# Interface.net
KiCad netlist of a schematic drawn in Altium Designer
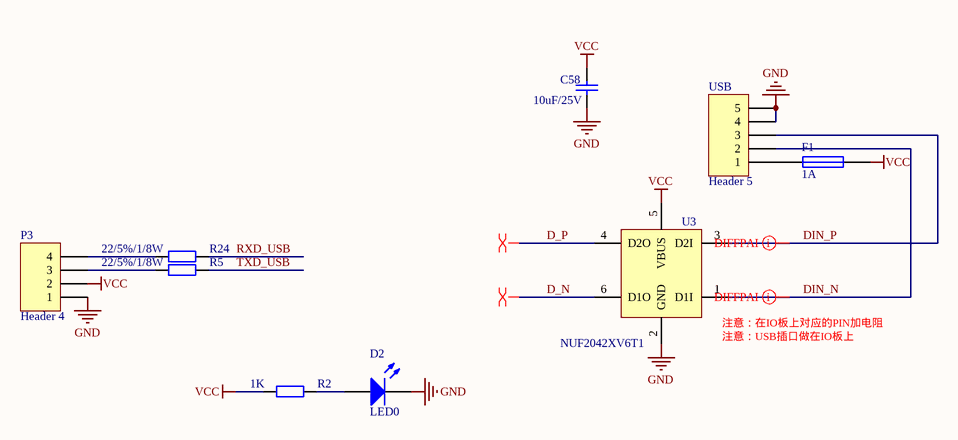
[diagram p0: Interface.SchDoc]

(export (version "E")
  (design (tool "Eeschema 10.0.6"))
  (components
    (comp (ref "C58")
      (value "10uF/25V")
      (footprint "0603C")
      (description "Capacitor")
      (fields (field (name "PUBLISHER") "Altium Limited"))
      (libsource (lib "Miscellaneous Devices") (part "Cap"))
    )
    (comp (ref "D2")
      (value "LED0")
      (footprint "0603LED")
      (description "Typical INFRARED GaAs LED")
      (fields (field (name "PUBLISHER") "Altium Limited"))
      (libsource (lib "Miscellaneous Devices") (part "LED0"))
    )
    (comp (ref "F1")
      (value "1A")
      (footprint "0805R")
      (description "Fuse")
      (fields (field (name "PUBLISHER") "Altium Limited"))
      (libsource (lib "Miscellaneous Devices") (part "Fuse 1"))
    )
    (comp (ref "P3")
      (value "Header 4")
      (footprint "HDR1X4")
      (description "Header, 4-Pin")
      (fields (field (name "PUBLISHER") "Altium Limited"))
      (libsource (lib "Miscellaneous Connectors") (part "Header 4"))
    )
    (comp (ref "R2")
      (value "1K")
      (footprint "0402R")
      (description "Resistor SMD - IEC symbol version")
      (libsource (lib "SX1276_e266v02a") (part "Resistor"))
    )
    (comp (ref "R5")
      (value "22/5%/1/8W")
      (footprint "0402R")
      (description "Resistor SMD - IEC symbol version")
      (libsource (lib "SX1276_e266v02a") (part "Resistor"))
    )
    (comp (ref "R24")
      (value "22/5%/1/8W")
      (footprint "0402R")
      (description "Resistor SMD - IEC symbol version")
      (libsource (lib "SX1276_e266v02a") (part "Resistor"))
    )
    (comp (ref "U3")
      (value "NUF2042XV6T1")
      (footprint "SOT563-6")
      (libsource (lib "Myself_1") (part "NUF2042XV6T1"))
    )
    (comp (ref "USB")
      (value "Header 5")
      (footprint "Micro_USB_PH")
      (description "Header, 5-Pin")
      (fields (field (name "PUBLISHER") "Altium Limited"))
      (libsource (lib "Miscellaneous Connectors") (part "Header 5"))
    )
  )
  (nets
    (net (code "1") (name "/DIN_N") (class "Default")
      (node (ref "U3") (pin "1") (pinfunction "D1I_1") (pintype "passive"))
      (node (ref "USB") (pin "2") (pinfunction "2_2") (pintype "passive"))
    )
    (net (code "2") (name "/DIN_P") (class "Default")
      (node (ref "U3") (pin "3") (pinfunction "D2I_3") (pintype "passive"))
      (node (ref "USB") (pin "3") (pinfunction "3_3") (pintype "passive"))
    )
    (net (code "3") (name "/D_N") (class "Default")
      (node (ref "U3") (pin "6") (pinfunction "D1O_6") (pintype "passive"))
    )
    (net (code "4") (name "/D_P") (class "Default")
      (node (ref "U3") (pin "4") (pinfunction "D2O_4") (pintype "passive"))
    )
    (net (code "5") (name "/RXD_USB") (class "Default")
      (node (ref "R24") (pin "2") (pinfunction "2_2") (pintype "passive"))
    )
    (net (code "6") (name "/TXD_USB") (class "Default")
      (node (ref "R5") (pin "2") (pinfunction "2_2") (pintype "passive"))
    )
    (net (code "7") (name "GND") (class "Default")
      (node (ref "C58") (pin "1") (pinfunction "1_1") (pintype "passive"))
      (node (ref "D2") (pin "2") (pinfunction "K_2") (pintype "passive"))
      (node (ref "P3") (pin "1") (pinfunction "1_1") (pintype "passive"))
      (node (ref "U3") (pin "2") (pinfunction "GND_2") (pintype "passive"))
      (node (ref "USB") (pin "4") (pinfunction "4_4") (pintype "passive"))
      (node (ref "USB") (pin "5") (pinfunction "5_5") (pintype "passive"))
    )
    (net (code "8") (name "Net-(D2-A)") (class "Default")
      (node (ref "D2") (pin "1") (pinfunction "A_1") (pintype "passive"))
      (node (ref "R2") (pin "2") (pinfunction "2_2") (pintype "passive"))
    )
    (net (code "9") (name "Net-(F1-Pad1)") (class "Default")
      (node (ref "F1") (pin "1") (pinfunction "1_1") (pintype "passive"))
      (node (ref "USB") (pin "1") (pinfunction "1_1") (pintype "passive"))
    )
    (net (code "10") (name "Net-(P3-Pad3)") (class "Default")
      (node (ref "P3") (pin "3") (pinfunction "3_3") (pintype "passive"))
      (node (ref "R5") (pin "1") (pinfunction "1_1") (pintype "passive"))
    )
    (net (code "11") (name "Net-(P3-Pad4)") (class "Default")
      (node (ref "P3") (pin "4") (pinfunction "4_4") (pintype "passive"))
      (node (ref "R24") (pin "1") (pinfunction "1_1") (pintype "passive"))
    )
    (net (code "12") (name "VCC") (class "Default")
      (node (ref "C58") (pin "2") (pinfunction "2_2") (pintype "passive"))
      (node (ref "F1") (pin "2") (pinfunction "2_2") (pintype "passive"))
      (node (ref "P3") (pin "2") (pinfunction "2_2") (pintype "passive"))
      (node (ref "R2") (pin "1") (pinfunction "1_1") (pintype "passive"))
      (node (ref "U3") (pin "5") (pinfunction "VBUS_5") (pintype "passive"))
    )
  )
)
